# DualRail_TPS6513x.net
KiCad netlist of a schematic drawn in Altium Designer
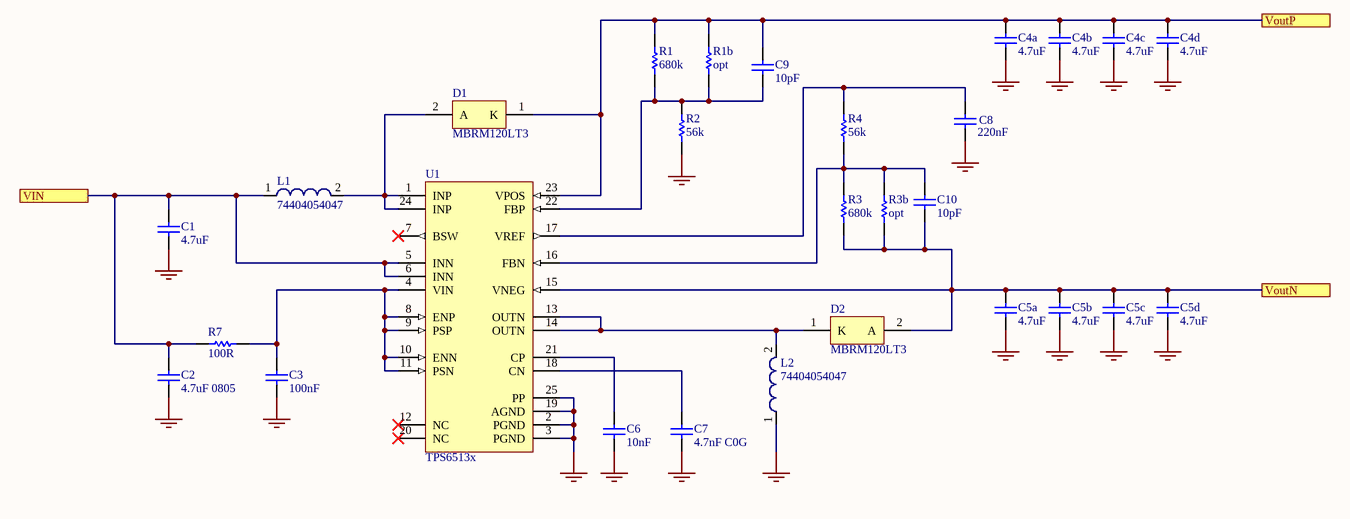
[diagram p0: DualRail_TPS6513x.SchDoc]

(export (version "E")
  (design (tool "Eeschema 10.0.6"))
  (components
    (comp (ref "C1")
      (value "4.7uF")
      (footprint "CAPC1206(3216)190_L")
      (description "CAP 4.7uF 25V ±20% 1206 (3216 Metric) Thickness 1.9mm SMD")
      (fields (field (name "TOLERANCE") "Â±20%"))
      (libsource (lib "Altium Content Vault") (part "CAP"))
    )
    (comp (ref "C2")
      (value "4.7uF 0805")
      (footprint "CAPC0805(2012)155_N")
      (description "CAP 4.7uF 10V ±10% 0805 (2012 Metric) Thickness 1.55mm SMD")
      (fields (field (name "TOLERANCE") "Â±10%"))
      (libsource (lib "Altium Content Vault") (part "CAP"))
    )
    (comp (ref "C3")
      (value "100nF")
      (footprint "CAPC0603(1608)100_L")
      (description "CAP 100nF 25V ±20% 0603 (1608 Metric) Thickness 1mm SMD")
      (fields (field (name "TOLERANCE") "Â±20%"))
      (libsource (lib "Altium Content Vault") (part "CAP"))
    )
    (comp (ref "C4a")
      (value "4.7uF")
      (footprint "CAPC1206(3216)190_L")
      (description "CAP 4.7uF 25V ±20% 1206 (3216 Metric) Thickness 1.9mm SMD")
      (fields (field (name "TOLERANCE") "Â±20%"))
      (libsource (lib "Altium Content Vault") (part "CAP"))
    )
    (comp (ref "C4b")
      (value "4.7uF")
      (footprint "CAPC1206(3216)190_L")
      (description "CAP 4.7uF 25V ±20% 1206 (3216 Metric) Thickness 1.9mm SMD")
      (fields (field (name "TOLERANCE") "Â±20%"))
      (libsource (lib "Altium Content Vault") (part "CAP"))
    )
    (comp (ref "C4c")
      (value "4.7uF")
      (footprint "CAPC1206(3216)190_L")
      (description "CAP 4.7uF 25V ±20% 1206 (3216 Metric) Thickness 1.9mm SMD")
      (fields (field (name "TOLERANCE") "Â±20%"))
      (libsource (lib "Altium Content Vault") (part "CAP"))
    )
    (comp (ref "C4d")
      (value "4.7uF")
      (footprint "CAPC1206(3216)190_L")
      (description "CAP 4.7uF 25V ±20% 1206 (3216 Metric) Thickness 1.9mm SMD")
      (fields (field (name "TOLERANCE") "Â±20%"))
      (libsource (lib "Altium Content Vault") (part "CAP"))
    )
    (comp (ref "C5a")
      (value "4.7uF")
      (footprint "CAPC1206(3216)190_L")
      (description "CAP 4.7uF 25V ±20% 1206 (3216 Metric) Thickness 1.9mm SMD")
      (fields (field (name "TOLERANCE") "Â±20%"))
      (libsource (lib "Altium Content Vault") (part "CAP"))
    )
    (comp (ref "C5b")
      (value "4.7uF")
      (footprint "CAPC1206(3216)190_L")
      (description "CAP 4.7uF 25V ±20% 1206 (3216 Metric) Thickness 1.9mm SMD")
      (fields (field (name "TOLERANCE") "Â±20%"))
      (libsource (lib "Altium Content Vault") (part "CAP"))
    )
    (comp (ref "C5c")
      (value "4.7uF")
      (footprint "CAPC1206(3216)190_L")
      (description "CAP 4.7uF 25V ±20% 1206 (3216 Metric) Thickness 1.9mm SMD")
      (fields (field (name "TOLERANCE") "Â±20%"))
      (libsource (lib "Altium Content Vault") (part "CAP"))
    )
    (comp (ref "C5d")
      (value "4.7uF")
      (footprint "CAPC1206(3216)190_L")
      (description "CAP 4.7uF 25V ±20% 1206 (3216 Metric) Thickness 1.9mm SMD")
      (fields (field (name "TOLERANCE") "Â±20%"))
      (libsource (lib "Altium Content Vault") (part "CAP"))
    )
    (comp (ref "C6")
      (value "10nF")
      (footprint "CAPC0603(1608)100_L")
      (description "CAP 100nF 25V ±20% 0603 (1608 Metric) Thickness 1mm SMD")
      (fields (field (name "TOLERANCE") "Â±20%"))
      (libsource (lib "Altium Content Vault") (part "CAP"))
    )
    (comp (ref "C7")
      (value "4.7nF C0G")
      (footprint "CAPC0805(2012)75_L")
      (description "CAP 4.7nF 50V ±20% 0805 (2012 Metric) Thickness 0.75mm SMD")
      (fields (field (name "TOLERANCE") "Â±20%"))
      (libsource (lib "Altium Content Vault") (part "CAP"))
    )
    (comp (ref "C8")
      (value "220nF")
      (footprint "CAPC0603(1608)100_L")
      (description "CAP 220nF 10V ±5% 0603 (1608 Metric) Thickness 1mm SMD")
      (fields (field (name "TOLERANCE") "Â±5%"))
      (libsource (lib "Altium Content Vault") (part "CAP"))
    )
    (comp (ref "C9")
      (value "10pF")
      (footprint "CAPC0603(1608)100_L")
      (fields (field (name "TOLERANCE") "Â±5%"))
      (libsource (lib "Altium Content Vault") (part "CAP"))
    )
    (comp (ref "C10")
      (value "10pF")
      (footprint "CAPC0603(1608)100_L")
      (fields (field (name "TOLERANCE") "Â±5%"))
      (libsource (lib "Altium Content Vault") (part "CAP"))
    )
    (comp (ref "D1")
      (value "MBRM120LT3")
      (footprint "ONSC-POWERMITE-2-457-04_D_V")
      (description "Schottky Power Rectifier, 2-Pin Powermite, Tape and Reel")
      (fields (field (name "MANUFACTURER") "On Semiconductor"))
      (libsource (lib "Altium Content Vault") (part "ONSC-D-K1A2-2_A"))
    )
    (comp (ref "D2")
      (value "MBRM120LT3")
      (footprint "ONSC-POWERMITE-2-457-04_D_V")
      (description "Schottky Power Rectifier, 2-Pin Powermite, Tape and Reel")
      (fields (field (name "MANUFACTURER") "On Semiconductor"))
      (libsource (lib "") (part "ONSC-D-K1A2-2_A_1"))
    )
    (comp (ref "L1")
      (value "74404054047")
      (footprint "WE-LQS 5040")
      (description "WE-LQS SMD Power Inductor, L=4.7 µH")
      (fields (field (name "MANUFACTURER") "Wuerth Elektronik"))
      (libsource (lib "Altium Content Vault") (part "WE-IND-INDUCTOR-2"))
    )
    (comp (ref "L2")
      (value "74404054047")
      (footprint "WE-LQS 5040")
      (description "WE-LQS SMD Power Inductor, L=4.7 µH")
      (fields (field (name "MANUFACTURER") "Wuerth Elektronik"))
      (libsource (lib "Altium Content Vault") (part "WE-IND-INDUCTOR-2"))
    )
    (comp (ref "R1")
      (value "680k")
      (footprint "RESC0603(1608)_L")
      (fields (field (name "TOLERANCE") "1 %") (field (name "POWER") "0.1 W"))
      (libsource (lib "Altium Content Vault") (part "RES"))
    )
    (comp (ref "R1b")
      (value "opt")
      (footprint "RESC0603(1608)_L")
      (fields (field (name "TOLERANCE") "1 %") (field (name "POWER") "0.1 W"))
      (libsource (lib "Altium Content Vault") (part "RES"))
    )
    (comp (ref "R2")
      (value "56k")
      (footprint "RESC0603(1608)_L")
      (fields (field (name "TOLERANCE") "1 %") (field (name "POWER") "0.1 W"))
      (libsource (lib "Altium Content Vault") (part "RES"))
    )
    (comp (ref "R3")
      (value "680k")
      (footprint "RESC0603(1608)_L")
      (fields (field (name "TOLERANCE") "1 %") (field (name "POWER") "0.1 W"))
      (libsource (lib "Altium Content Vault") (part "RES"))
    )
    (comp (ref "R3b")
      (value "opt")
      (footprint "RESC0603(1608)_L")
      (fields (field (name "TOLERANCE") "1 %") (field (name "POWER") "0.1 W"))
      (libsource (lib "Altium Content Vault") (part "RES"))
    )
    (comp (ref "R4")
      (value "56k")
      (footprint "RESC0603(1608)_L")
      (fields (field (name "TOLERANCE") "1 %") (field (name "POWER") "0.1 W"))
      (libsource (lib "Altium Content Vault") (part "RES"))
    )
    (comp (ref "R7")
      (value "100R")
      (footprint "RESC0603(1608)_L")
      (description "100R 0.1W 1% 0603 (1608 Metric)  SMD")
      (fields (field (name "TOLERANCE") "1 %") (field (name "POWER") "0.1 W"))
      (libsource (lib "Altium Content Vault") (part "RES"))
    )
    (comp (ref "U1")
      (value "TPS6513x")
      (footprint "TI-RGE24-2450X2450TP_V")
      (description "TPS65130 or TPS65131 Postive and Negative Output DC-DC Converter")
      (fields (field (name "PARTNUMBER") "TPS65130RGET") (field (name "MANUFACTURER") "Texas Instruments"))
      (libsource (lib "Altium Content Vault") (part "TI-TPS65130RGE24-2450X2450TP"))
    )
  )
  (nets
    (net (code "1") (name "/VIN") (class "Default")
      (node (ref "C1") (pin "2") (pinfunction "2_2") (pintype "passive"))
      (node (ref "C2") (pin "2") (pinfunction "2_2") (pintype "passive"))
      (node (ref "L1") (pin "1") (pinfunction "1_1") (pintype "passive"))
      (node (ref "R7") (pin "2") (pinfunction "2_2") (pintype "passive"))
      (node (ref "U1") (pin "5") (pinfunction "INN_5") (pintype "power_in"))
      (node (ref "U1") (pin "6") (pinfunction "INN_6") (pintype "power_in"))
    )
    (net (code "2") (name "/VoutN") (class "Default")
      (node (ref "C10") (pin "2") (pinfunction "2_2") (pintype "passive"))
      (node (ref "C5a") (pin "2") (pinfunction "2_2") (pintype "passive"))
      (node (ref "C5b") (pin "2") (pinfunction "2_2") (pintype "passive"))
      (node (ref "C5c") (pin "2") (pinfunction "2_2") (pintype "passive"))
      (node (ref "C5d") (pin "2") (pinfunction "2_2") (pintype "passive"))
      (node (ref "D2") (pin "2") (pinfunction "A_2") (pintype "passive"))
      (node (ref "R3") (pin "2") (pinfunction "2_2") (pintype "passive"))
      (node (ref "R3b") (pin "2") (pinfunction "2_2") (pintype "passive"))
      (node (ref "U1") (pin "15") (pinfunction "VNEG_15") (pintype "input"))
    )
    (net (code "3") (name "/VoutP") (class "Default")
      (node (ref "C4a") (pin "2") (pinfunction "2_2") (pintype "passive"))
      (node (ref "C4b") (pin "2") (pinfunction "2_2") (pintype "passive"))
      (node (ref "C4c") (pin "2") (pinfunction "2_2") (pintype "passive"))
      (node (ref "C4d") (pin "2") (pinfunction "2_2") (pintype "passive"))
      (node (ref "C9") (pin "2") (pinfunction "2_2") (pintype "passive"))
      (node (ref "D1") (pin "1") (pinfunction "K_1") (pintype "passive"))
      (node (ref "R1") (pin "1") (pinfunction "1_1") (pintype "passive"))
      (node (ref "R1b") (pin "1") (pinfunction "1_1") (pintype "passive"))
      (node (ref "U1") (pin "23") (pinfunction "VPOS_23") (pintype "input"))
    )
    (net (code "4") (name "GND") (class "Default")
      (node (ref "C1") (pin "1") (pinfunction "1_1") (pintype "passive"))
      (node (ref "C2") (pin "1") (pinfunction "1_1") (pintype "passive"))
      (node (ref "C3") (pin "1") (pinfunction "1_1") (pintype "passive"))
      (node (ref "C4a") (pin "1") (pinfunction "1_1") (pintype "passive"))
      (node (ref "C4b") (pin "1") (pinfunction "1_1") (pintype "passive"))
      (node (ref "C4c") (pin "1") (pinfunction "1_1") (pintype "passive"))
      (node (ref "C4d") (pin "1") (pinfunction "1_1") (pintype "passive"))
      (node (ref "C5a") (pin "1") (pinfunction "1_1") (pintype "passive"))
      (node (ref "C5b") (pin "1") (pinfunction "1_1") (pintype "passive"))
      (node (ref "C5c") (pin "1") (pinfunction "1_1") (pintype "passive"))
      (node (ref "C5d") (pin "1") (pinfunction "1_1") (pintype "passive"))
      (node (ref "C6") (pin "1") (pinfunction "1_1") (pintype "passive"))
      (node (ref "C7") (pin "1") (pinfunction "1_1") (pintype "passive"))
      (node (ref "C8") (pin "1") (pinfunction "1_1") (pintype "passive"))
      (node (ref "L2") (pin "1") (pinfunction "1_1") (pintype "passive"))
      (node (ref "R2") (pin "2") (pinfunction "2_2") (pintype "passive"))
      (node (ref "U1") (pin "19") (pinfunction "AGND_19") (pintype "power_in"))
      (node (ref "U1") (pin "2") (pinfunction "PGND_2") (pintype "power_in"))
      (node (ref "U1") (pin "25") (pinfunction "PP_25") (pintype "power_in"))
      (node (ref "U1") (pin "3") (pinfunction "PGND_3") (pintype "power_in"))
    )
    (net (code "5") (name "Net-(D1-A)") (class "Default")
      (node (ref "D1") (pin "2") (pinfunction "A_2") (pintype "passive"))
      (node (ref "L1") (pin "2") (pinfunction "2_2") (pintype "passive"))
      (node (ref "U1") (pin "1") (pinfunction "INP_1") (pintype "power_in"))
      (node (ref "U1") (pin "24") (pinfunction "INP_24") (pintype "power_in"))
    )
    (net (code "6") (name "Net-(D2-K)") (class "Default")
      (node (ref "D2") (pin "1") (pinfunction "K_1") (pintype "passive"))
      (node (ref "L2") (pin "2") (pinfunction "2_2") (pintype "passive"))
      (node (ref "U1") (pin "13") (pinfunction "OUTN_13") (pintype "power_in"))
      (node (ref "U1") (pin "14") (pinfunction "OUTN_14") (pintype "power_in"))
    )
    (net (code "7") (name "Net-(U1-CN)") (class "Default")
      (node (ref "C7") (pin "2") (pinfunction "2_2") (pintype "passive"))
      (node (ref "U1") (pin "18") (pinfunction "CN_18") (pintype "passive"))
    )
    (net (code "8") (name "Net-(U1-CP)") (class "Default")
      (node (ref "C6") (pin "2") (pinfunction "2_2") (pintype "passive"))
      (node (ref "U1") (pin "21") (pinfunction "CP_21") (pintype "passive"))
    )
    (net (code "9") (name "Net-(U1-ENN)") (class "Default")
      (node (ref "C3") (pin "2") (pinfunction "2_2") (pintype "passive"))
      (node (ref "R7") (pin "1") (pinfunction "1_1") (pintype "passive"))
      (node (ref "U1") (pin "10") (pinfunction "ENN_10") (pintype "input"))
      (node (ref "U1") (pin "11") (pinfunction "PSN_11") (pintype "input"))
      (node (ref "U1") (pin "4") (pinfunction "VIN_4") (pintype "power_in"))
      (node (ref "U1") (pin "8") (pinfunction "ENP_8") (pintype "input"))
      (node (ref "U1") (pin "9") (pinfunction "PSP_9") (pintype "input"))
    )
    (net (code "10") (name "Net-(U1-FBN)") (class "Default")
      (node (ref "C10") (pin "1") (pinfunction "1_1") (pintype "passive"))
      (node (ref "R3") (pin "1") (pinfunction "1_1") (pintype "passive"))
      (node (ref "R3b") (pin "1") (pinfunction "1_1") (pintype "passive"))
      (node (ref "R4") (pin "2") (pinfunction "2_2") (pintype "passive"))
      (node (ref "U1") (pin "16") (pinfunction "FBN_16") (pintype "input"))
    )
    (net (code "11") (name "Net-(U1-FBP)") (class "Default")
      (node (ref "C9") (pin "1") (pinfunction "1_1") (pintype "passive"))
      (node (ref "R1") (pin "2") (pinfunction "2_2") (pintype "passive"))
      (node (ref "R1b") (pin "2") (pinfunction "2_2") (pintype "passive"))
      (node (ref "R2") (pin "1") (pinfunction "1_1") (pintype "passive"))
      (node (ref "U1") (pin "22") (pinfunction "FBP_22") (pintype "input"))
    )
    (net (code "12") (name "Net-(U1-VREF)") (class "Default")
      (node (ref "C8") (pin "2") (pinfunction "2_2") (pintype "passive"))
      (node (ref "R4") (pin "1") (pinfunction "1_1") (pintype "passive"))
      (node (ref "U1") (pin "17") (pinfunction "VREF_17") (pintype "output"))
    )
    (net (code "13") (name "unconnected-(U1-BSW-Pad7)") (class "Default")
      (node (ref "U1") (pin "7") (pinfunction "BSW_7") (pintype "output+no_connect"))
    )
    (net (code "14") (name "unconnected-(U1-NC-Pad12)") (class "Default")
      (node (ref "U1") (pin "12") (pinfunction "NC_12") (pintype "passive+no_connect"))
    )
    (net (code "15") (name "unconnected-(U1-NC-Pad20)") (class "Default")
      (node (ref "U1") (pin "20") (pinfunction "NC_20") (pintype "passive+no_connect"))
    )
  )
)
